# Programmer.net
KiCad netlist of a schematic drawn in EAGLE
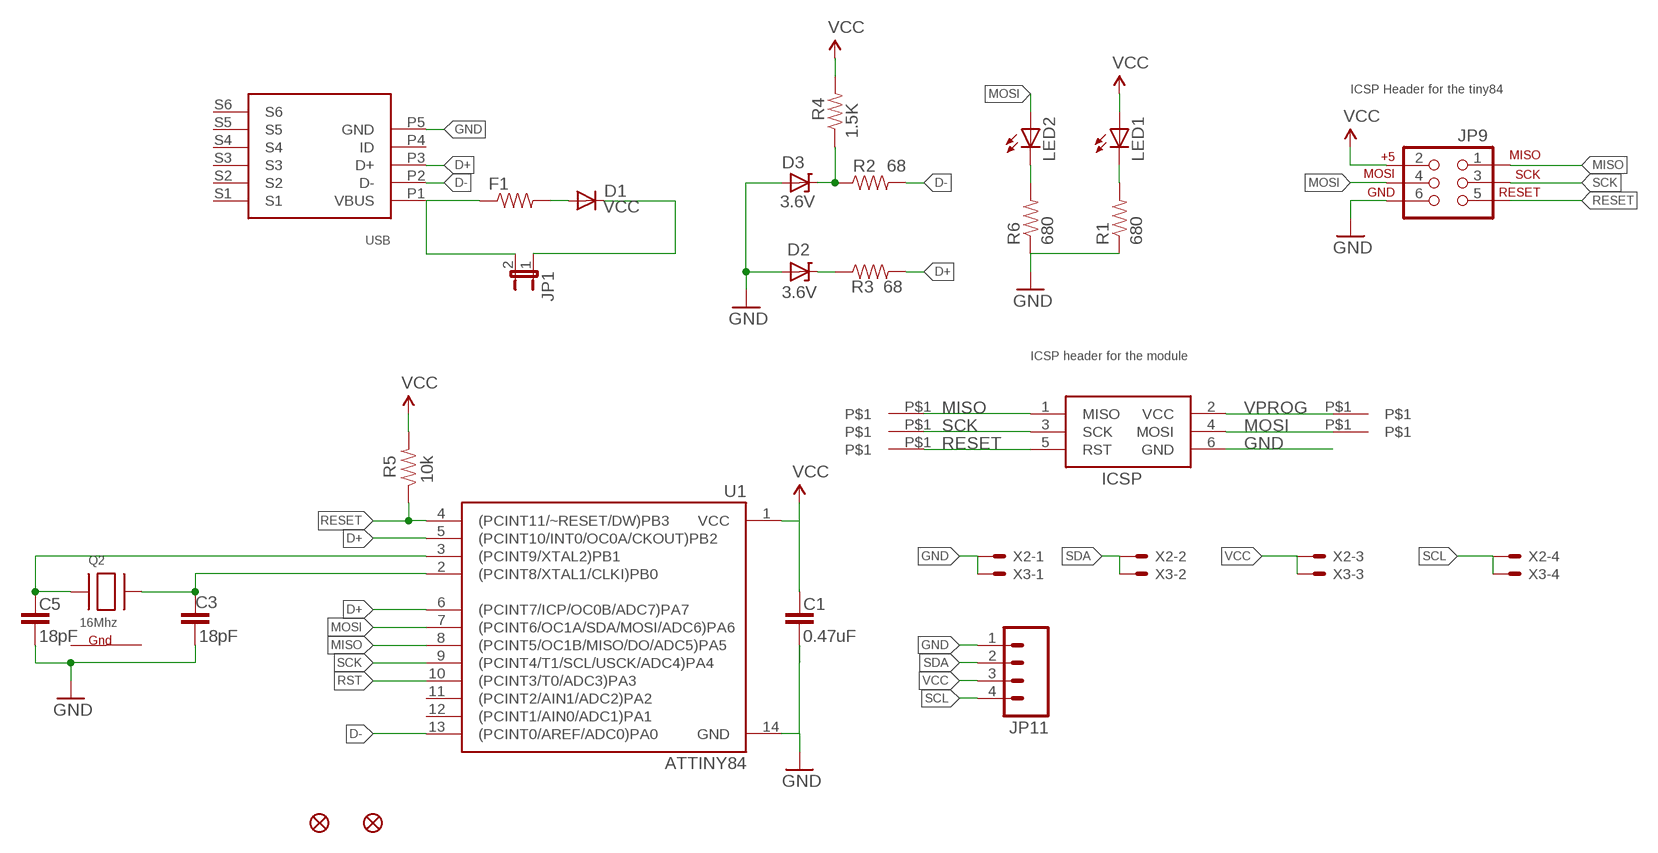
[diagram p0: schematic, sheet 1]

(export (version "E")
  (design (tool "Eeschema 10.0.6"))
  (components
    (comp (ref "C1")
      (value "0.47uF")
      (footprint "eagle-import:0805")
      (libsource (lib "eagle-import") (part "CAP0805"))
    )
    (comp (ref "C3")
      (value "18pF")
      (footprint "eagle-import:0805")
      (libsource (lib "eagle-import") (part "CAP0805"))
    )
    (comp (ref "C5")
      (value "18pF")
      (footprint "eagle-import:0805")
      (libsource (lib "eagle-import") (part "CAP0805"))
    )
    (comp (ref "D1")
      (value "DIODESMB")
      (footprint "eagle-import:SMB-DIODE")
      (libsource (lib "eagle-import") (part "DIODESMB"))
    )
    (comp (ref "D2")
      (value "3.6V")
      (footprint "eagle-import:SOD-323")
      (libsource (lib "eagle-import") (part "DIODE-ZENER-BZT52"))
    )
    (comp (ref "D3")
      (value "3.6V")
      (footprint "eagle-import:SOD-323")
      (libsource (lib "eagle-import") (part "DIODE-ZENER-BZT52"))
    )
    (comp (ref "F1")
      (value "RESISTOR0805-RES")
      (footprint "eagle-import:0805")
      (libsource (lib "eagle-import") (part "RESISTOR0805-RES"))
    )
    (comp (ref "ICSP")
      (value "AVRISP-BOX")
      (footprint "eagle-import:AVRISP-BOX")
      (libsource (lib "eagle-import") (part "AVRISP-BOX"))
    )
    (comp (ref "JP1")
      (value "JUMPER-2SMD-NO")
      (footprint "eagle-import:SJ_2S-NO")
      (libsource (lib "eagle-import") (part "JUMPER-2SMD-NO"))
    )
    (comp (ref "JP8")
      (value "FIDUCIALUFIDUCIAL")
      (footprint "eagle-import:MICRO-FIDUCIAL")
      (libsource (lib "eagle-import") (part "FIDUCIALUFIDUCIAL"))
    )
    (comp (ref "JP9")
      (value "AVR_SPI_PRG_6PTH")
      (footprint "eagle-import:2X3")
      (libsource (lib "eagle-import") (part "AVR_SPI_PRG_6PTH"))
    )
    (comp (ref "JP10")
      (value "FIDUCIALUFIDUCIAL")
      (footprint "eagle-import:MICRO-FIDUCIAL")
      (libsource (lib "eagle-import") (part "FIDUCIALUFIDUCIAL"))
    )
    (comp (ref "JP11")
      (value "M04LOCK")
      (footprint "eagle-import:1X04_LOCK")
      (libsource (lib "eagle-import") (part "M04LOCK"))
    )
    (comp (ref "LED1")
      (value "LEDCHIPLED_0805")
      (footprint "eagle-import:CHIPLED_0805")
      (libsource (lib "eagle-import") (part "LEDCHIPLED_0805"))
    )
    (comp (ref "LED2")
      (value "LEDCHIPLED_0805")
      (footprint "eagle-import:CHIPLED_0805")
      (libsource (lib "eagle-import") (part "LEDCHIPLED_0805"))
    )
    (comp (ref "Q2")
      (value "16Mhz")
      (footprint "eagle-import:NX3225")
      (libsource (lib "eagle-import") (part "XTAL-4-3225"))
    )
    (comp (ref "R1")
      (value "680")
      (footprint "eagle-import:0805")
      (libsource (lib "eagle-import") (part "RESISTOR0805-RES"))
    )
    (comp (ref "R2")
      (value "68")
      (footprint "eagle-import:0805")
      (libsource (lib "eagle-import") (part "SparkFun-Resistors_RESISTOR0805-RES"))
    )
    (comp (ref "R3")
      (value "68")
      (footprint "eagle-import:0805")
      (libsource (lib "eagle-import") (part "SparkFun-Resistors_RESISTOR0805-RES"))
    )
    (comp (ref "R4")
      (value "1.5K")
      (footprint "eagle-import:0805")
      (libsource (lib "eagle-import") (part "SparkFun-Resistors_RESISTOR0805-RES"))
    )
    (comp (ref "R5")
      (value "10k")
      (footprint "eagle-import:0402-RES")
      (libsource (lib "eagle-import") (part "RESISTOR0402-RES"))
    )
    (comp (ref "R6")
      (value "680")
      (footprint "eagle-import:0805")
      (libsource (lib "eagle-import") (part "RESISTOR0805-RES"))
    )
    (comp (ref "U$1")
      (value "SPRING-CONNECTOR")
      (footprint "eagle-import:SPRING-CONNECTOR")
      (libsource (lib "eagle-import") (part "SPRING-CONNECTOR"))
    )
    (comp (ref "U$2")
      (value "SPRING-CONNECTOR")
      (footprint "eagle-import:SPRING-CONNECTOR")
      (libsource (lib "eagle-import") (part "SPRING-CONNECTOR"))
    )
    (comp (ref "U$15")
      (value "USBFCI-MICROB")
      (footprint "eagle-import:USB-MICROB-FCI")
      (libsource (lib "eagle-import") (part "USBFCI-MICROB"))
    )
    (comp (ref "U$22")
      (value "SPRING-CONNECTOR")
      (footprint "eagle-import:SPRING-CONNECTOR")
      (libsource (lib "eagle-import") (part "SPRING-CONNECTOR"))
    )
    (comp (ref "U$23")
      (value "SPRING-CONNECTOR")
      (footprint "eagle-import:SPRING-CONNECTOR")
      (libsource (lib "eagle-import") (part "SPRING-CONNECTOR"))
    )
    (comp (ref "U$24")
      (value "SPRING-CONNECTOR")
      (footprint "eagle-import:SPRING-CONNECTOR")
      (libsource (lib "eagle-import") (part "SPRING-CONNECTOR"))
    )
    (comp (ref "U1")
      (value "ATTINY84")
      (footprint "eagle-import:SO14")
      (libsource (lib "eagle-import") (part "ATTINY84"))
    )
    (comp (ref "X2")
      (value "C-GRID-04-70543")
      (footprint "eagle-import:70543-04")
      (libsource (lib "eagle-import") (part "C-GRID-04-70543"))
    )
    (comp (ref "X3")
      (value "C-GRID-04-70543")
      (footprint "eagle-import:70543-04")
      (libsource (lib "eagle-import") (part "C-GRID-04-70543"))
    )
  )
  (nets
    (net (code "1") (name "/G1") (class "Default")
      (node (ref "Q2") (pin "4") (pinfunction "G1_4") (pintype "power_in"))
    )
    (net (code "2") (name "/G2") (class "Default")
      (node (ref "Q2") (pin "2") (pinfunction "G2_2") (pintype "power_in"))
    )
    (net (code "3") (name "/VPROG") (class "Default")
      (node (ref "ICSP") (pin "2") (pinfunction "VCC_2") (pintype "power_in"))
      (node (ref "U$24") (pin "P$1") (pinfunction "P$1_P$1") (pintype "bidirectional"))
    )
    (net (code "4") (name "D+") (class "Default")
      (node (ref "R3") (pin "2") (pinfunction "2_2") (pintype "passive"))
      (node (ref "U$15") (pin "P3") (pinfunction "D+_P3") (pintype "bidirectional"))
      (node (ref "U1") (pin "5") (pinfunction "(PCINT10/INT0/OC0A/CKOUT)PB2_5") (pintype "bidirectional"))
      (node (ref "U1") (pin "6") (pinfunction "(PCINT7/ICP/OC0B/ADC7)PA7_6") (pintype "bidirectional"))
    )
    (net (code "5") (name "D-") (class "Default")
      (node (ref "R2") (pin "2") (pinfunction "2_2") (pintype "passive"))
      (node (ref "U$15") (pin "P2") (pinfunction "D-_P2") (pintype "bidirectional"))
      (node (ref "U1") (pin "13") (pinfunction "(PCINT0/AREF/ADC0)PA0_13") (pintype "bidirectional"))
    )
    (net (code "6") (name "GND") (class "Default")
      (node (ref "C1") (pin "2") (pinfunction "2_2") (pintype "passive"))
      (node (ref "C3") (pin "2") (pinfunction "2_2") (pintype "passive"))
      (node (ref "C5") (pin "2") (pinfunction "2_2") (pintype "passive"))
      (node (ref "D2") (pin "2") (pinfunction "A_2") (pintype "passive"))
      (node (ref "D3") (pin "2") (pinfunction "A_2") (pintype "passive"))
      (node (ref "ICSP") (pin "6") (pinfunction "GND_6") (pintype "power_in"))
      (node (ref "JP11") (pin "1") (pinfunction "1_1") (pintype "passive"))
      (node (ref "JP9") (pin "6") (pinfunction "6_6") (pintype "passive"))
      (node (ref "R1") (pin "1") (pinfunction "1_1") (pintype "passive"))
      (node (ref "R6") (pin "1") (pinfunction "1_1") (pintype "passive"))
      (node (ref "U$15") (pin "P5") (pinfunction "GND_P5") (pintype "bidirectional"))
      (node (ref "U1") (pin "14") (pinfunction "GND_14") (pintype "bidirectional"))
      (node (ref "X2") (pin "1") (pinfunction "S_1") (pintype "passive"))
      (node (ref "X3") (pin "1") (pinfunction "S_1") (pintype "passive"))
    )
    (net (code "7") (name "MISO") (class "Default")
      (node (ref "ICSP") (pin "1") (pinfunction "MISO_1") (pintype "input"))
      (node (ref "JP9") (pin "1") (pinfunction "1_1") (pintype "passive"))
      (node (ref "U$1") (pin "P$1") (pinfunction "P$1_P$1") (pintype "bidirectional"))
      (node (ref "U1") (pin "8") (pinfunction "(PCINT5/OC1B/MISO/DO/ADC5)PA5_8") (pintype "bidirectional"))
    )
    (net (code "8") (name "MOSI") (class "Default")
      (node (ref "ICSP") (pin "4") (pinfunction "MOSI_4") (pintype "output"))
      (node (ref "JP9") (pin "4") (pinfunction "4_4") (pintype "passive"))
      (node (ref "LED2") (pin "A") (pinfunction "A_A") (pintype "passive"))
      (node (ref "U$23") (pin "P$1") (pinfunction "P$1_P$1") (pintype "bidirectional"))
      (node (ref "U1") (pin "7") (pinfunction "(PCINT6/OC1A/SDA/MOSI/ADC6)PA6_7") (pintype "bidirectional"))
    )
    (net (code "9") (name "Net-(D1-PadA)") (class "Default")
      (node (ref "D1") (pin "A") (pinfunction "A_A") (pintype "passive"))
      (node (ref "F1") (pin "2") (pinfunction "2_2") (pintype "passive"))
    )
    (net (code "10") (name "Net-(D2-C)") (class "Default")
      (node (ref "D2") (pin "1") (pinfunction "C_1") (pintype "passive"))
      (node (ref "R3") (pin "1") (pinfunction "1_1") (pintype "passive"))
    )
    (net (code "11") (name "Net-(D3-C)") (class "Default")
      (node (ref "D3") (pin "1") (pinfunction "C_1") (pintype "passive"))
      (node (ref "R2") (pin "1") (pinfunction "1_1") (pintype "passive"))
      (node (ref "R4") (pin "1") (pinfunction "1_1") (pintype "passive"))
    )
    (net (code "12") (name "Net-(LED1-PadC)") (class "Default")
      (node (ref "LED1") (pin "C") (pinfunction "C_C") (pintype "passive"))
      (node (ref "R1") (pin "2") (pinfunction "2_2") (pintype "passive"))
    )
    (net (code "13") (name "Net-(LED2-PadC)") (class "Default")
      (node (ref "LED2") (pin "C") (pinfunction "C_C") (pintype "passive"))
      (node (ref "R6") (pin "2") (pinfunction "2_2") (pintype "passive"))
    )
    (net (code "14") (name "Net-(Q2-X1)") (class "Default")
      (node (ref "C5") (pin "1") (pinfunction "1_1") (pintype "passive"))
      (node (ref "Q2") (pin "1") (pinfunction "X1_1") (pintype "bidirectional"))
      (node (ref "U1") (pin "3") (pinfunction "(PCINT9/XTAL2)PB1_3") (pintype "bidirectional"))
    )
    (net (code "15") (name "Net-(Q2-X2)") (class "Default")
      (node (ref "C3") (pin "1") (pinfunction "1_1") (pintype "passive"))
      (node (ref "Q2") (pin "3") (pinfunction "X2_3") (pintype "bidirectional"))
      (node (ref "U1") (pin "2") (pinfunction "(PCINT8/XTAL1/CLKI)PB0_2") (pintype "bidirectional"))
    )
    (net (code "16") (name "Net-(U$15-VBUS)") (class "Default")
      (node (ref "F1") (pin "1") (pinfunction "1_1") (pintype "passive"))
      (node (ref "JP1") (pin "2") (pinfunction "2_2") (pintype "passive"))
      (node (ref "U$15") (pin "P1") (pinfunction "VBUS_P1") (pintype "bidirectional"))
    )
    (net (code "17") (name "RESET") (class "Default")
      (node (ref "ICSP") (pin "5") (pinfunction "RST_5") (pintype "output"))
      (node (ref "JP9") (pin "5") (pinfunction "5_5") (pintype "passive"))
      (node (ref "R5") (pin "1") (pinfunction "1_1") (pintype "passive"))
      (node (ref "U$2") (pin "P$1") (pinfunction "P$1_P$1") (pintype "bidirectional"))
      (node (ref "U1") (pin "4") (pinfunction "(PCINT11/~{RESET/DW})PB3_4") (pintype "bidirectional"))
    )
    (net (code "18") (name "RST") (class "Default")
      (node (ref "U1") (pin "10") (pinfunction "(PCINT3/T0/ADC3)PA3_10") (pintype "bidirectional"))
    )
    (net (code "19") (name "SCK") (class "Default")
      (node (ref "ICSP") (pin "3") (pinfunction "SCK_3") (pintype "output"))
      (node (ref "JP9") (pin "3") (pinfunction "3_3") (pintype "passive"))
      (node (ref "U$22") (pin "P$1") (pinfunction "P$1_P$1") (pintype "bidirectional"))
      (node (ref "U1") (pin "9") (pinfunction "(PCINT4/T1/SCL/USCK/ADC4)PA4_9") (pintype "bidirectional"))
    )
    (net (code "20") (name "SCL") (class "Default")
      (node (ref "JP11") (pin "4") (pinfunction "4_4") (pintype "passive"))
      (node (ref "X2") (pin "4") (pinfunction "S_4") (pintype "passive"))
      (node (ref "X3") (pin "4") (pinfunction "S_4") (pintype "passive"))
    )
    (net (code "21") (name "SDA") (class "Default")
      (node (ref "JP11") (pin "2") (pinfunction "2_2") (pintype "passive"))
      (node (ref "X2") (pin "2") (pinfunction "S_2") (pintype "passive"))
      (node (ref "X3") (pin "2") (pinfunction "S_2") (pintype "passive"))
    )
    (net (code "22") (name "VCC") (class "Default")
      (node (ref "C1") (pin "1") (pinfunction "1_1") (pintype "passive"))
      (node (ref "D1") (pin "C") (pinfunction "C_C") (pintype "passive"))
      (node (ref "JP1") (pin "1") (pinfunction "1_1") (pintype "passive"))
      (node (ref "JP11") (pin "3") (pinfunction "3_3") (pintype "passive"))
      (node (ref "JP9") (pin "2") (pinfunction "2_2") (pintype "passive"))
      (node (ref "LED1") (pin "A") (pinfunction "A_A") (pintype "passive"))
      (node (ref "R4") (pin "2") (pinfunction "2_2") (pintype "passive"))
      (node (ref "R5") (pin "2") (pinfunction "2_2") (pintype "passive"))
      (node (ref "U1") (pin "1") (pinfunction "VCC_1") (pintype "bidirectional"))
      (node (ref "X2") (pin "3") (pinfunction "S_3") (pintype "passive"))
      (node (ref "X3") (pin "3") (pinfunction "S_3") (pintype "passive"))
    )
    (net (code "23") (name "unconnected-(U$15-ID-PadP4)") (class "Default")
      (node (ref "U$15") (pin "P4") (pinfunction "ID_P4") (pintype "bidirectional"))
    )
    (net (code "24") (name "unconnected-(U$15-PadS1)") (class "Default")
      (node (ref "U$15") (pin "S1") (pinfunction "S1_S1") (pintype "bidirectional"))
    )
    (net (code "25") (name "unconnected-(U$15-PadS2)") (class "Default")
      (node (ref "U$15") (pin "S2") (pinfunction "S2_S2") (pintype "bidirectional"))
    )
    (net (code "26") (name "unconnected-(U$15-PadS3)") (class "Default")
      (node (ref "U$15") (pin "S3") (pinfunction "S3_S3") (pintype "bidirectional"))
    )
    (net (code "27") (name "unconnected-(U$15-PadS4)") (class "Default")
      (node (ref "U$15") (pin "S4") (pinfunction "S4_S4") (pintype "bidirectional"))
    )
    (net (code "28") (name "unconnected-(U$15-PadS5)") (class "Default")
      (node (ref "U$15") (pin "S5") (pinfunction "S5_S5") (pintype "bidirectional"))
    )
    (net (code "29") (name "unconnected-(U$15-PadS6)") (class "Default")
      (node (ref "U$15") (pin "S6") (pinfunction "S6_S6") (pintype "bidirectional"))
    )
    (net (code "30") (name "unconnected-(U1-(PCINT1{slash}AIN0{slash}ADC1)PA1-Pad12)") (class "Default")
      (node (ref "U1") (pin "12") (pinfunction "(PCINT1/AIN0/ADC1)PA1_12") (pintype "bidirectional"))
    )
    (net (code "31") (name "unconnected-(U1-(PCINT2{slash}AIN1{slash}ADC2)PA2-Pad11)") (class "Default")
      (node (ref "U1") (pin "11") (pinfunction "(PCINT2/AIN1/ADC2)PA2_11") (pintype "bidirectional"))
    )
  )
)
